# TremorMug_Final.net
KiCad netlist of a schematic drawn in EAGLE
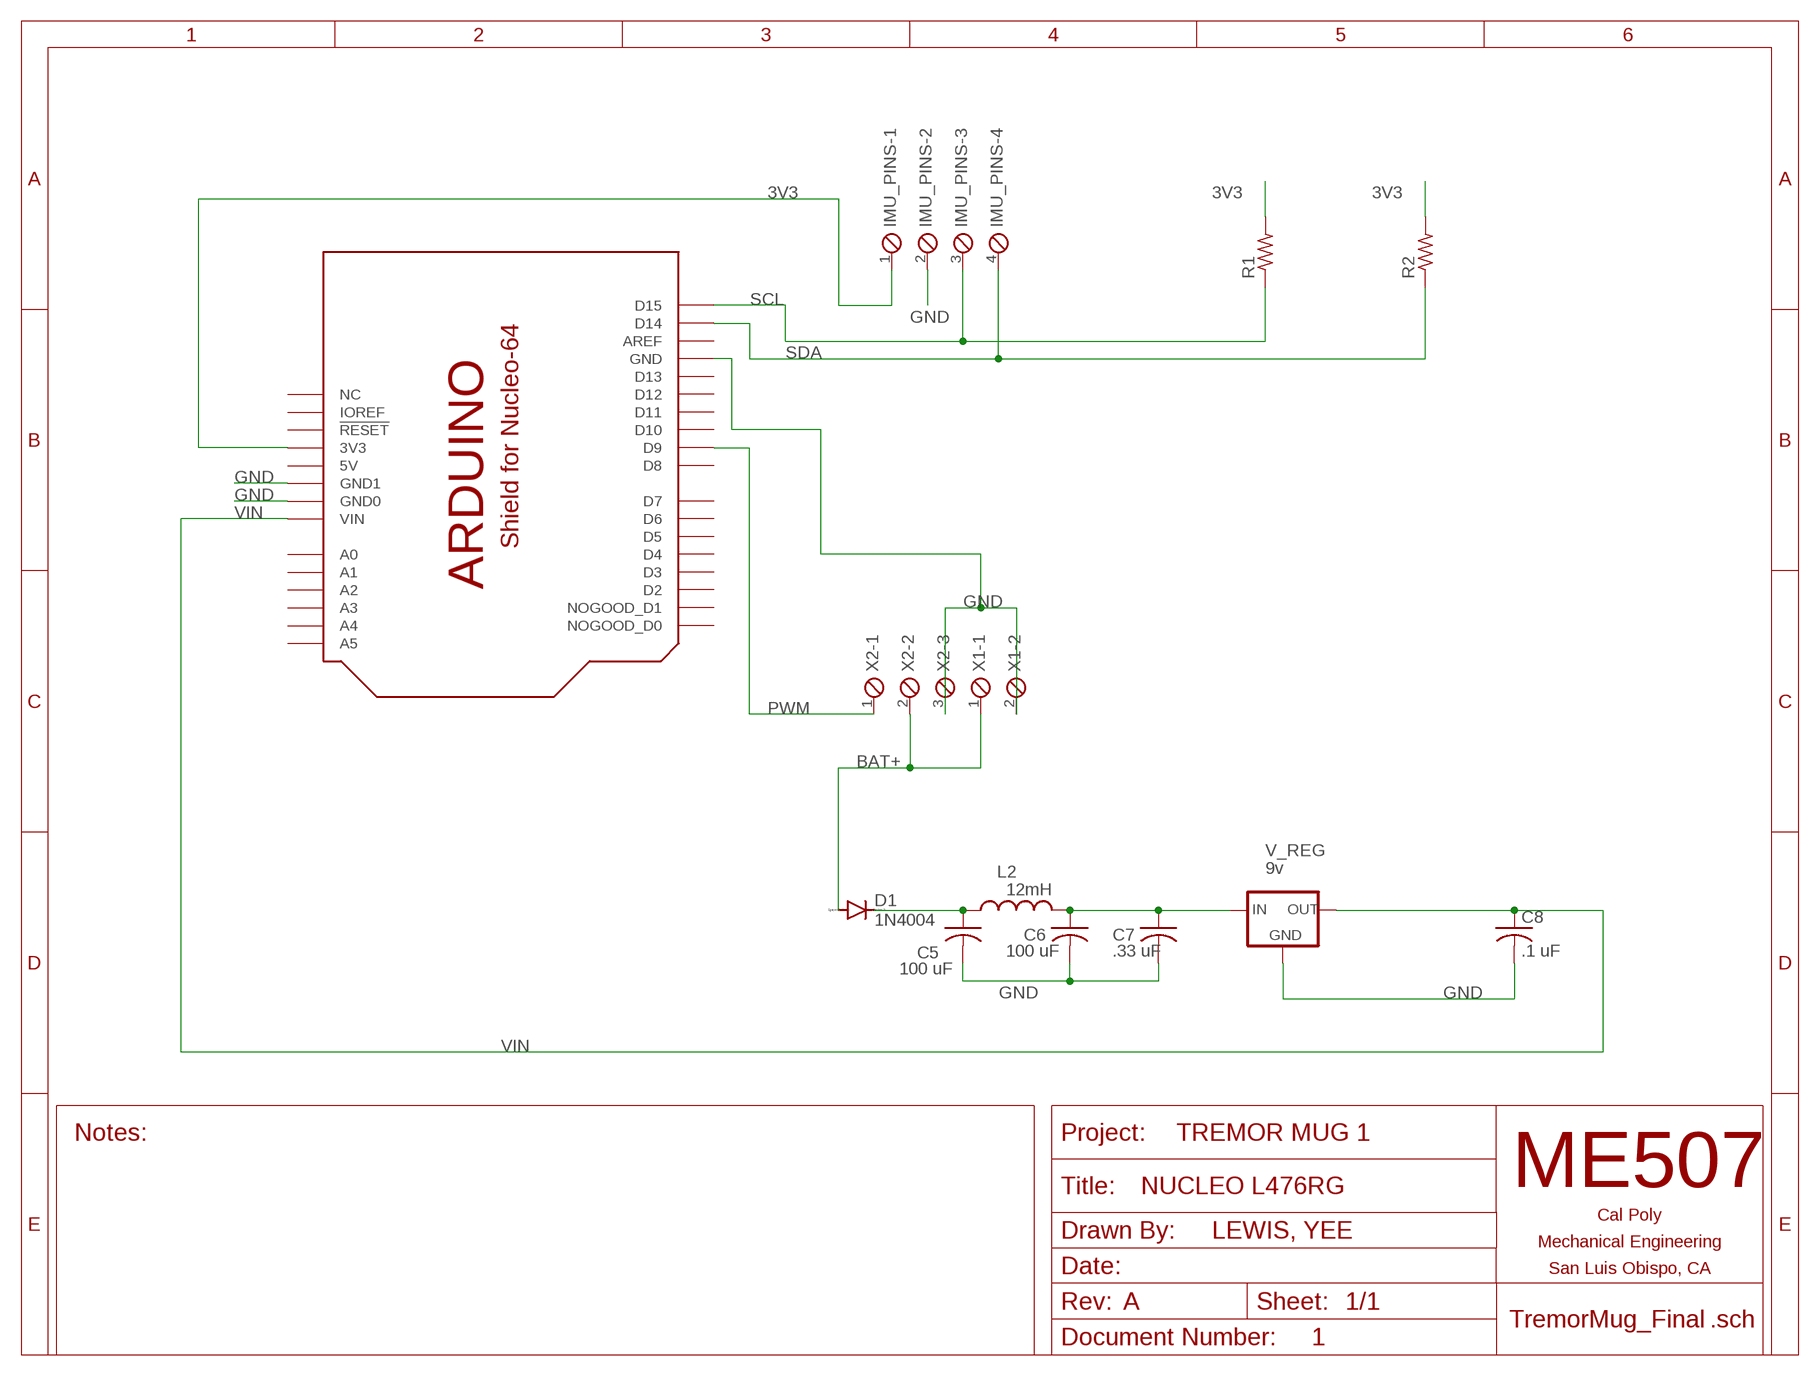
[diagram p0: schematic, sheet 1]

(export (version "E")
  (design (tool "Eeschema 10.0.6"))
  (components
    (comp (ref "C5")
      (value "100 uF")
      (footprint "eagle-import:C050-045X075")
      (libsource (lib "eagle-import") (part "C-US050-045X075"))
    )
    (comp (ref "C6")
      (value "100 uF")
      (footprint "eagle-import:C050-045X075")
      (libsource (lib "eagle-import") (part "C-US050-045X075"))
    )
    (comp (ref "C7")
      (value ".33 uF")
      (footprint "eagle-import:C0805")
      (libsource (lib "eagle-import") (part "C-USC0805"))
    )
    (comp (ref "C8")
      (value ".1 uF")
      (footprint "eagle-import:C0805")
      (libsource (lib "eagle-import") (part "C-USC0805"))
    )
    (comp (ref "D1")
      (value "1N4004")
      (footprint "eagle-import:DO41-10")
      (libsource (lib "eagle-import") (part "1N4004"))
    )
    (comp (ref "IMU_PINS")
      (value "SCREWTERM_4P_254")
      (footprint "eagle-import:4POL254")
      (libsource (lib "eagle-import") (part "SCREWTERM_4P_254"))
    )
    (comp (ref "L2")
      (value "12mH")
      (footprint "eagle-import:0207_5V")
      (libsource (lib "eagle-import") (part "L-US0207/5V"))
    )
    (comp (ref "R1")
      (value "R-US_0204/7")
      (footprint "eagle-import:0204_7")
      (libsource (lib "eagle-import") (part "R-US_0204/7"))
    )
    (comp (ref "R2")
      (value "R-US_0204/7")
      (footprint "eagle-import:0204_7")
      (libsource (lib "eagle-import") (part "R-US_0204/7"))
    )
    (comp (ref "U$1")
      (value "SHIELD_FOR_NUCLE0_64_STANDARD")
      (footprint "eagle-import:SHIELD_FOR_NUCLEO_64_STD")
      (libsource (lib "eagle-import") (part "SHIELD_FOR_NUCLE0_64_STANDARD"))
    )
    (comp (ref "V_REG")
      (value "9v")
      (footprint "eagle-import:78MXXL")
      (libsource (lib "eagle-import") (part "78MXXL"))
    )
    (comp (ref "X1")
      (value "SCREWTERM_2P_508")
      (footprint "eagle-import:2POL508")
      (libsource (lib "eagle-import") (part "SCREWTERM_2P_508"))
    )
    (comp (ref "X2")
      (value "SCREWTERM_3P_381")
      (footprint "eagle-import:3POL381")
      (libsource (lib "eagle-import") (part "SCREWTERM_3P_381"))
    )
  )
  (nets
    (net (code "1") (name "/3V3") (class "Default")
      (node (ref "IMU_PINS") (pin "1") (pinfunction "1_1") (pintype "passive"))
      (node (ref "R1") (pin "2") (pinfunction "2_2") (pintype "passive"))
      (node (ref "R2") (pin "2") (pinfunction "2_2") (pintype "passive"))
      (node (ref "U$1") (pin "3V") (pinfunction "3V3_3V") (pintype "power_in"))
    )
    (net (code "2") (name "/5V") (class "Default")
      (node (ref "U$1") (pin "5V") (pinfunction "5V_5V") (pintype "power_in"))
    )
    (net (code "3") (name "/BAT+") (class "Default")
      (node (ref "D1") (pin "A") (pinfunction "A_A") (pintype "passive"))
      (node (ref "X1") (pin "1") (pinfunction "1_1") (pintype "passive"))
      (node (ref "X2") (pin "2") (pinfunction "1_2") (pintype "passive"))
    )
    (net (code "4") (name "/GND") (class "Default")
      (node (ref "C5") (pin "2") (pinfunction "2_2") (pintype "passive"))
      (node (ref "C6") (pin "2") (pinfunction "2_2") (pintype "passive"))
      (node (ref "C7") (pin "2") (pinfunction "2_2") (pintype "passive"))
      (node (ref "C8") (pin "2") (pinfunction "2_2") (pintype "passive"))
      (node (ref "IMU_PINS") (pin "2") (pinfunction "1_2") (pintype "passive"))
      (node (ref "U$1") (pin "GND") (pinfunction "GND_GND") (pintype "power_in"))
      (node (ref "U$1") (pin "GND1") (pinfunction "GND0_GND1") (pintype "power_in"))
      (node (ref "U$1") (pin "GND2") (pinfunction "GND1_GND2") (pintype "power_in"))
      (node (ref "V_REG") (pin "GND") (pinfunction "GND_GND") (pintype "input"))
      (node (ref "X1") (pin "2") (pinfunction "1_2") (pintype "passive"))
      (node (ref "X2") (pin "3") (pinfunction "1_3") (pintype "passive"))
    )
    (net (code "5") (name "/PWM") (class "Default")
      (node (ref "U$1") (pin "D9") (pinfunction "D9_D9") (pintype "bidirectional"))
      (node (ref "X2") (pin "1") (pinfunction "1_1") (pintype "passive"))
    )
    (net (code "6") (name "/SCL") (class "Default")
      (node (ref "IMU_PINS") (pin "3") (pinfunction "1_3") (pintype "passive"))
      (node (ref "R1") (pin "1") (pinfunction "1_1") (pintype "passive"))
      (node (ref "U$1") (pin "D15") (pinfunction "D15_D15") (pintype "bidirectional"))
    )
    (net (code "7") (name "/SDA") (class "Default")
      (node (ref "IMU_PINS") (pin "4") (pinfunction "1_4") (pintype "passive"))
      (node (ref "R2") (pin "1") (pinfunction "1_1") (pintype "passive"))
      (node (ref "U$1") (pin "D14") (pinfunction "D14_D14") (pintype "bidirectional"))
    )
    (net (code "8") (name "/VIN") (class "Default")
      (node (ref "C8") (pin "1") (pinfunction "1_1") (pintype "passive"))
      (node (ref "U$1") (pin "VIN") (pinfunction "VIN_VIN") (pintype "power_in"))
      (node (ref "V_REG") (pin "OUT") (pinfunction "OUT_OUT") (pintype "passive"))
    )
    (net (code "9") (name "Net-(C5-Pad1)") (class "Default")
      (node (ref "C5") (pin "1") (pinfunction "1_1") (pintype "passive"))
      (node (ref "D1") (pin "C") (pinfunction "C_C") (pintype "passive"))
      (node (ref "L2") (pin "1") (pinfunction "1_1") (pintype "passive"))
    )
    (net (code "10") (name "Net-(C6-Pad1)") (class "Default")
      (node (ref "C6") (pin "1") (pinfunction "1_1") (pintype "passive"))
      (node (ref "C7") (pin "1") (pinfunction "1_1") (pintype "passive"))
      (node (ref "L2") (pin "2") (pinfunction "2_2") (pintype "passive"))
      (node (ref "V_REG") (pin "IN") (pinfunction "IN_IN") (pintype "input"))
    )
    (net (code "11") (name "unconnected-(U$1-NOGOOD_D0-PadD0)") (class "Default")
      (node (ref "U$1") (pin "D0") (pinfunction "NOGOOD_D0_D0") (pintype "no_connect"))
    )
    (net (code "12") (name "unconnected-(U$1-NOGOOD_D1-PadD1)") (class "Default")
      (node (ref "U$1") (pin "D1") (pinfunction "NOGOOD_D1_D1") (pintype "no_connect"))
    )
    (net (code "13") (name "unconnected-(U$1-PadA0)") (class "Default")
      (node (ref "U$1") (pin "A0") (pinfunction "A0_A0") (pintype "bidirectional"))
    )
    (net (code "14") (name "unconnected-(U$1-PadA1)") (class "Default")
      (node (ref "U$1") (pin "A1") (pinfunction "A1_A1") (pintype "bidirectional"))
    )
    (net (code "15") (name "unconnected-(U$1-PadA2)") (class "Default")
      (node (ref "U$1") (pin "A2") (pinfunction "A2_A2") (pintype "bidirectional"))
    )
    (net (code "16") (name "unconnected-(U$1-PadA3)") (class "Default")
      (node (ref "U$1") (pin "A3") (pinfunction "A3_A3") (pintype "bidirectional"))
    )
    (net (code "17") (name "unconnected-(U$1-PadA4)") (class "Default")
      (node (ref "U$1") (pin "A4") (pinfunction "A4_A4") (pintype "bidirectional"))
    )
    (net (code "18") (name "unconnected-(U$1-PadA5)") (class "Default")
      (node (ref "U$1") (pin "A5") (pinfunction "A5_A5") (pintype "bidirectional"))
    )
    (net (code "19") (name "unconnected-(U$1-PadAREF)") (class "Default")
      (node (ref "U$1") (pin "AREF") (pinfunction "AREF_AREF") (pintype "bidirectional"))
    )
    (net (code "20") (name "unconnected-(U$1-PadD2)") (class "Default")
      (node (ref "U$1") (pin "D2") (pinfunction "D2_D2") (pintype "bidirectional"))
    )
    (net (code "21") (name "unconnected-(U$1-PadD3)") (class "Default")
      (node (ref "U$1") (pin "D3") (pinfunction "D3_D3") (pintype "bidirectional"))
    )
    (net (code "22") (name "unconnected-(U$1-PadD4)") (class "Default")
      (node (ref "U$1") (pin "D4") (pinfunction "D4_D4") (pintype "bidirectional"))
    )
    (net (code "23") (name "unconnected-(U$1-PadD5)") (class "Default")
      (node (ref "U$1") (pin "D5") (pinfunction "D5_D5") (pintype "bidirectional"))
    )
    (net (code "24") (name "unconnected-(U$1-PadD6)") (class "Default")
      (node (ref "U$1") (pin "D6") (pinfunction "D6_D6") (pintype "bidirectional"))
    )
    (net (code "25") (name "unconnected-(U$1-PadD7)") (class "Default")
      (node (ref "U$1") (pin "D7") (pinfunction "D7_D7") (pintype "bidirectional"))
    )
    (net (code "26") (name "unconnected-(U$1-PadD8)") (class "Default")
      (node (ref "U$1") (pin "D8") (pinfunction "D8_D8") (pintype "bidirectional"))
    )
    (net (code "27") (name "unconnected-(U$1-PadD10)") (class "Default")
      (node (ref "U$1") (pin "D10") (pinfunction "D10_D10") (pintype "bidirectional"))
    )
    (net (code "28") (name "unconnected-(U$1-PadD11)") (class "Default")
      (node (ref "U$1") (pin "D11") (pinfunction "D11_D11") (pintype "bidirectional"))
    )
    (net (code "29") (name "unconnected-(U$1-PadD12)") (class "Default")
      (node (ref "U$1") (pin "D12") (pinfunction "D12_D12") (pintype "bidirectional"))
    )
    (net (code "30") (name "unconnected-(U$1-PadD13)") (class "Default")
      (node (ref "U$1") (pin "D13") (pinfunction "D13_D13") (pintype "bidirectional"))
    )
    (net (code "31") (name "unconnected-(U$1-PadIOREF)") (class "Default")
      (node (ref "U$1") (pin "IOREF") (pinfunction "IOREF_IOREF") (pintype "bidirectional"))
    )
    (net (code "32") (name "unconnected-(U$1-PadNC)") (class "Default")
      (node (ref "U$1") (pin "NC") (pinfunction "NC_NC") (pintype "no_connect"))
    )
    (net (code "33") (name "unconnected-(U$1-~{RESET}-PadNRST)") (class "Default")
      (node (ref "U$1") (pin "NRST") (pinfunction "~{RESET}_NRST") (pintype "input"))
    )
  )
)
